# Power_Supply_HV.net
KiCad netlist of a schematic drawn in Altium Designer
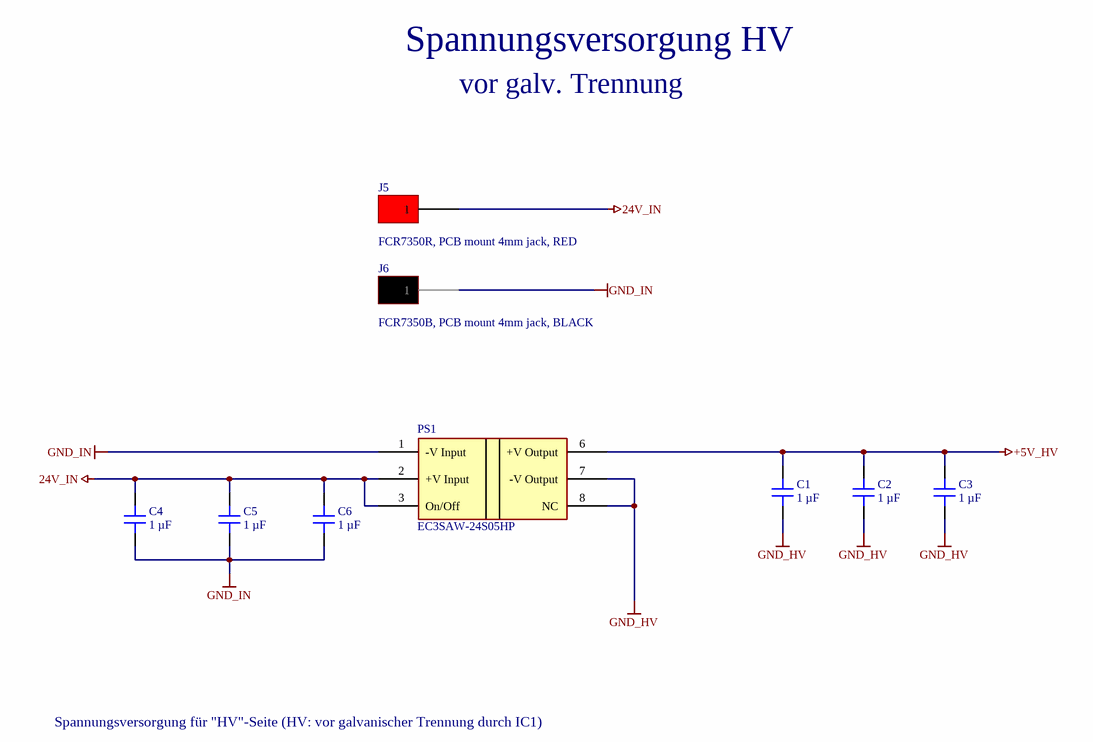
[diagram p0: Power_Supply_HV.SchDoc]

(export (version "E")
  (design (tool "Eeschema 10.0.6"))
  (components
    (comp (ref "C1")
      (value "1 µF")
      (footprint "C_0603")
      (description "50V 1uF X5R ±10% 0603  Multilayer Ceramic Capacitors MLCC - SMD/SMT ROHS")
      (fields
        (field (name "MANUFACTURER") "Samsung Electro-Mechanics")
        (field (name "MANUFACTURER PART NUMBER") "CL10A105KB8NNNC")
        (field (name "CREATED FROM") "MGremer")
      )
      (libsource (lib "user") (part "Capacitor"))
    )
    (comp (ref "C2")
      (value "1 µF")
      (footprint "C_0603")
      (description "50V 1uF X5R ±10% 0603  Multilayer Ceramic Capacitors MLCC - SMD/SMT ROHS")
      (fields
        (field (name "MANUFACTURER") "Samsung Electro-Mechanics")
        (field (name "MANUFACTURER PART NUMBER") "CL10A105KB8NNNC")
        (field (name "CREATED FROM") "MGremer")
      )
      (libsource (lib "user") (part "Capacitor"))
    )
    (comp (ref "C3")
      (value "1 µF")
      (footprint "C_0603")
      (description "50V 1uF X5R ±10% 0603  Multilayer Ceramic Capacitors MLCC - SMD/SMT ROHS")
      (fields
        (field (name "MANUFACTURER") "Samsung Electro-Mechanics")
        (field (name "MANUFACTURER PART NUMBER") "CL10A105KB8NNNC")
        (field (name "CREATED FROM") "MGremer")
      )
      (libsource (lib "user") (part "Capacitor"))
    )
    (comp (ref "C4")
      (value "1 µF")
      (footprint "C_0603")
      (description "50V 1uF X5R ±10% 0603  Multilayer Ceramic Capacitors MLCC - SMD/SMT ROHS")
      (fields
        (field (name "MANUFACTURER") "Samsung Electro-Mechanics")
        (field (name "MANUFACTURER PART NUMBER") "CL10A105KB8NNNC")
        (field (name "CREATED FROM") "MGremer")
      )
      (libsource (lib "user") (part "Capacitor"))
    )
    (comp (ref "C5")
      (value "1 µF")
      (footprint "C_0603")
      (description "50V 1uF X5R ±10% 0603  Multilayer Ceramic Capacitors MLCC - SMD/SMT ROHS")
      (fields
        (field (name "MANUFACTURER") "Samsung Electro-Mechanics")
        (field (name "MANUFACTURER PART NUMBER") "CL10A105KB8NNNC")
        (field (name "CREATED FROM") "MGremer")
      )
      (libsource (lib "user") (part "Capacitor"))
    )
    (comp (ref "C6")
      (value "1 µF")
      (footprint "C_0603")
      (description "50V 1uF X5R ±10% 0603  Multilayer Ceramic Capacitors MLCC - SMD/SMT ROHS")
      (fields
        (field (name "MANUFACTURER") "Samsung Electro-Mechanics")
        (field (name "MANUFACTURER PART NUMBER") "CL10A105KB8NNNC")
        (field (name "CREATED FROM") "MGremer")
      )
      (libsource (lib "user") (part "Capacitor"))
    )
    (comp (ref "J5")
      (value "FCR7350R, PCB mount 4mm jack, RED")
      (footprint "FCR7350")
      (description "FCR7350B, 1000V, 24A, RED")
      (fields
        (field (name "MANUFACTURER PART NUMBER") "FCR7350R")
        (field (name "MANUFACTURER") "Cliff")
        (field (name "CREATED FROM") "DHufnagel")
      )
      (libsource (lib "user") (part "FCR7350R"))
    )
    (comp (ref "J6")
      (value "FCR7350B, PCB mount 4mm jack, BLACK")
      (footprint "FCR7350")
      (description "FCR7350B, 1000V, 24A, BLACK")
      (fields
        (field (name "MANUFACTURER PART NUMBER") "FCR7350B")
        (field (name "MANUFACTURER") "Cliff")
        (field (name "CREATED FROM") "DHufnagel")
      )
      (libsource (lib "user") (part "FCR7350B"))
    )
    (comp (ref "PS1")
      (value "EC3SAW-24S05HP")
      (footprint "SamacSys:EC3SAW")
      (description "Isolierte DC/DC-Wandler – Durchsteckmontage 3W 9-36Vin 5Vout 600mA")
      (libsource (lib "SamacSys") (part "EC3SAW-24S05HP"))
    )
  )
  (nets
    (net (code "1") (name "+5V_HV") (class "Default")
      (node (ref "C1") (pin "1") (pinfunction "1_1") (pintype "passive"))
      (node (ref "C2") (pin "1") (pinfunction "1_1") (pintype "passive"))
      (node (ref "C3") (pin "1") (pinfunction "1_1") (pintype "passive"))
      (node (ref "PS1") (pin "6") (pinfunction "+V_Output_6") (pintype "power_in"))
    )
    (net (code "2") (name "24V_IN") (class "Default")
      (node (ref "C4") (pin "1") (pinfunction "1_1") (pintype "passive"))
      (node (ref "C5") (pin "1") (pinfunction "1_1") (pintype "passive"))
      (node (ref "C6") (pin "1") (pinfunction "1_1") (pintype "passive"))
      (node (ref "J5") (pin "1") (pinfunction "1_1") (pintype "passive"))
      (node (ref "PS1") (pin "2") (pinfunction "+V_Input_2") (pintype "power_in"))
      (node (ref "PS1") (pin "3") (pinfunction "On/Off_3") (pintype "passive"))
    )
    (net (code "3") (name "GND_HV") (class "Default")
      (node (ref "C1") (pin "2") (pinfunction "2_2") (pintype "passive"))
      (node (ref "C2") (pin "2") (pinfunction "2_2") (pintype "passive"))
      (node (ref "C3") (pin "2") (pinfunction "2_2") (pintype "passive"))
      (node (ref "PS1") (pin "7") (pinfunction "-V_Output_7") (pintype "power_in"))
      (node (ref "PS1") (pin "8") (pinfunction "NC_8") (pintype "passive"))
    )
    (net (code "4") (name "GND_IN") (class "Default")
      (node (ref "C4") (pin "2") (pinfunction "2_2") (pintype "passive"))
      (node (ref "C5") (pin "2") (pinfunction "2_2") (pintype "passive"))
      (node (ref "C6") (pin "2") (pinfunction "2_2") (pintype "passive"))
      (node (ref "J6") (pin "1") (pinfunction "1_1") (pintype "passive"))
      (node (ref "PS1") (pin "1") (pinfunction "-V_Input_1") (pintype "power_in"))
    )
  )
)
